# p6_wch_link.net
KiCad netlist of a schematic drawn in Altium Designer
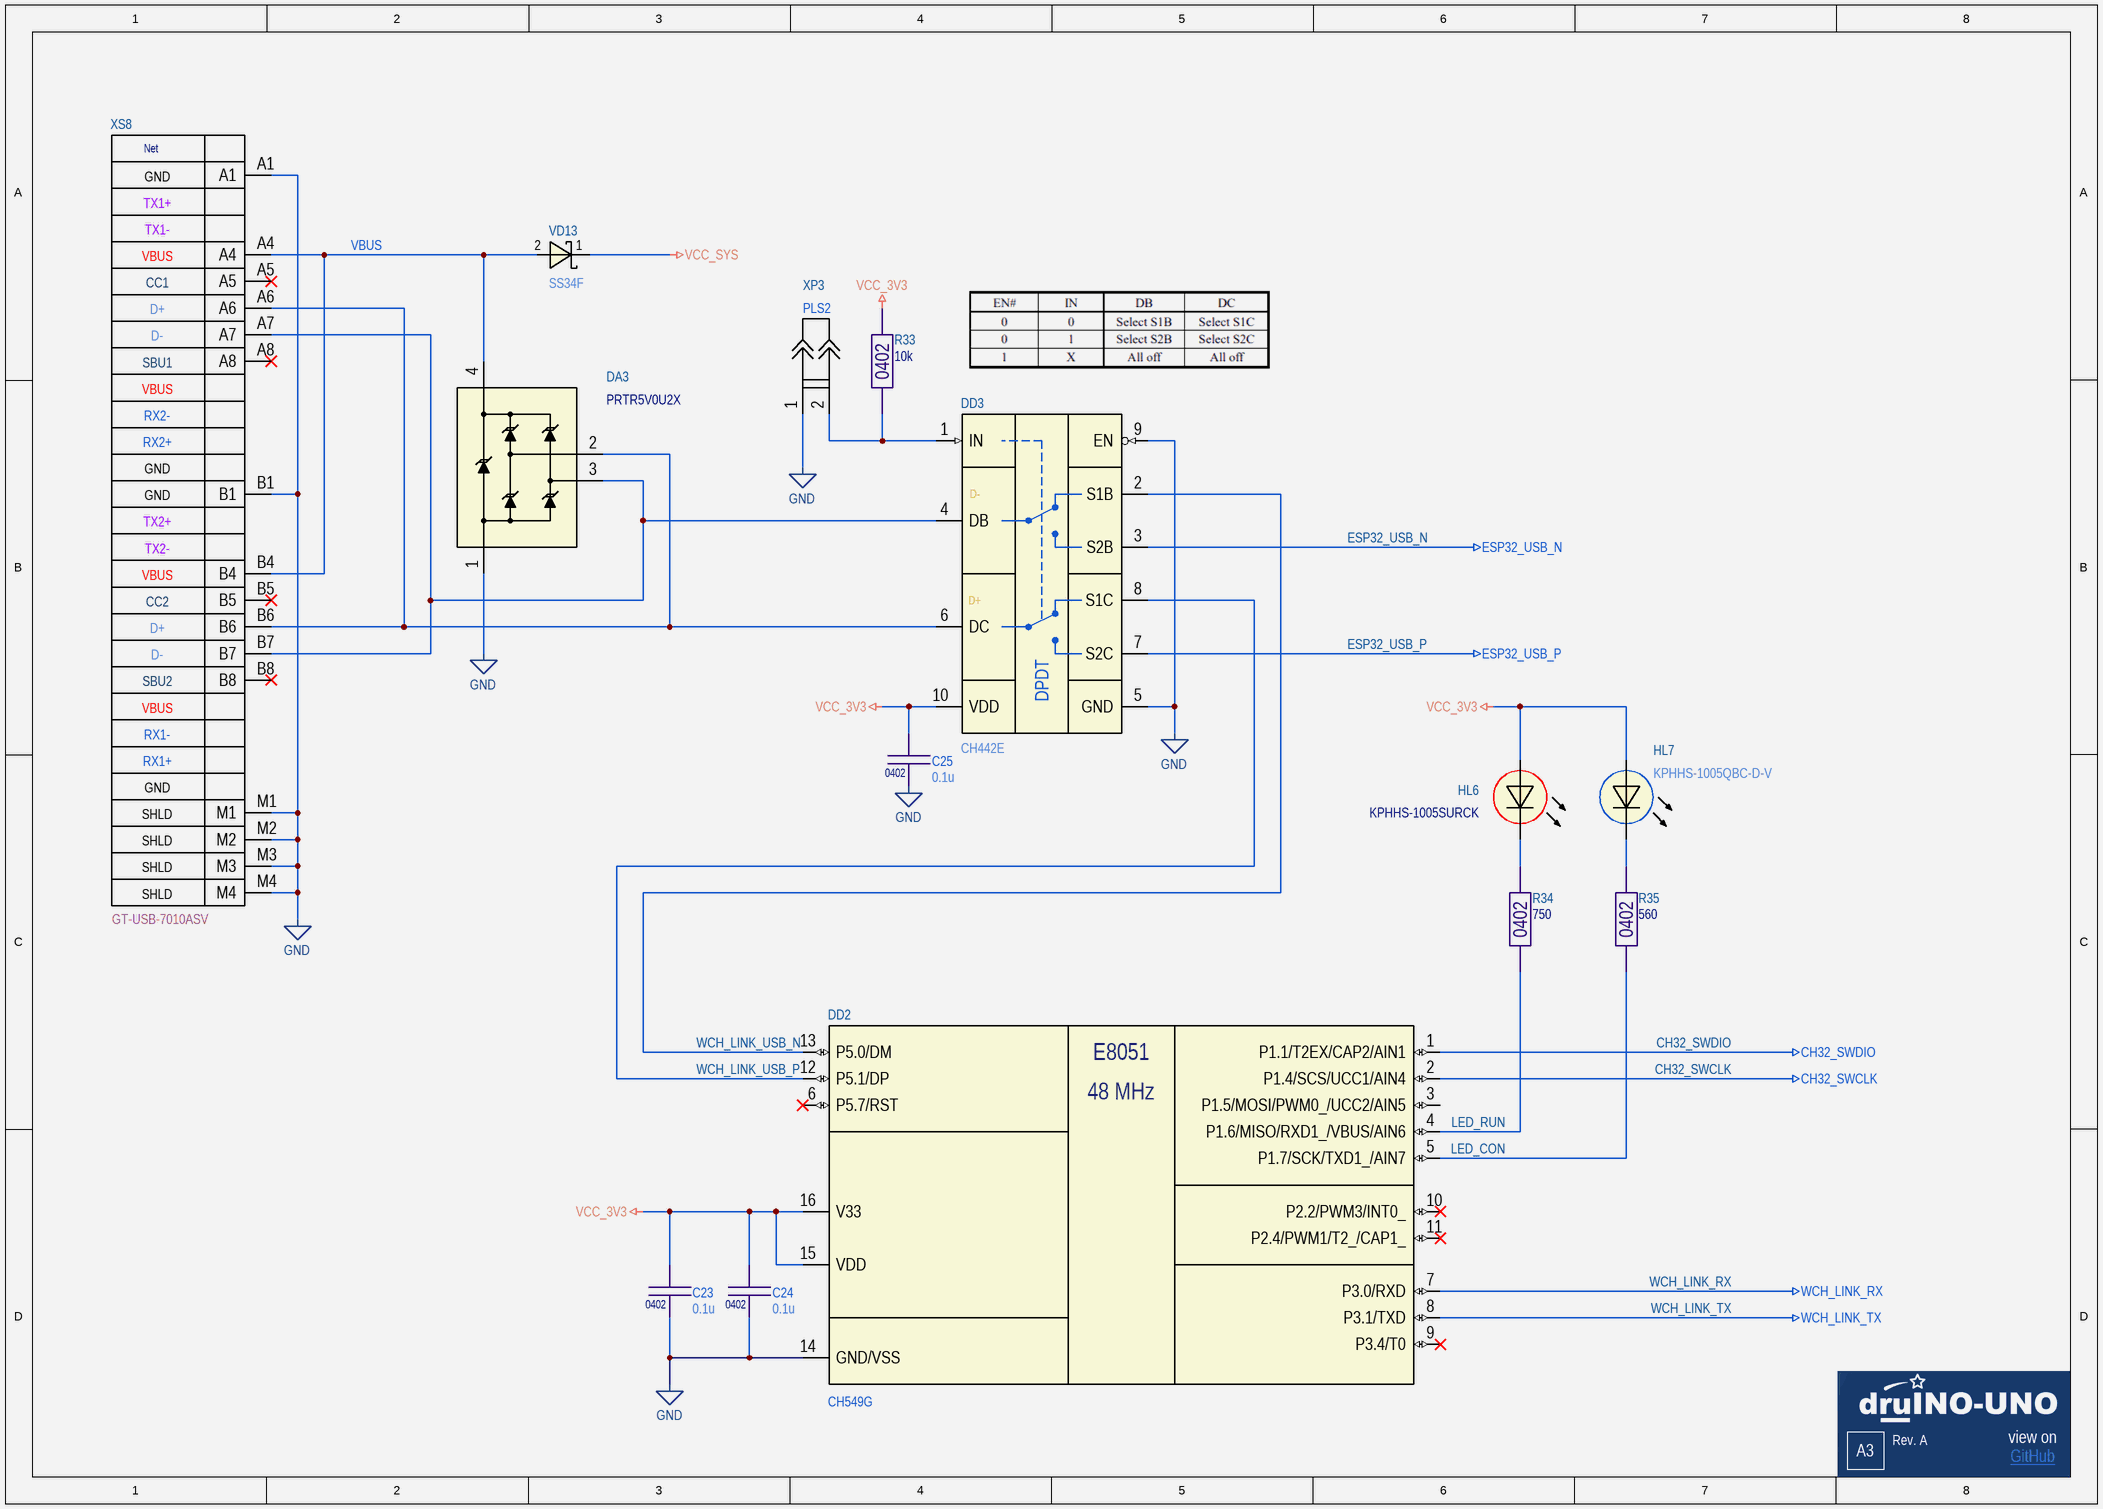
[diagram p0: p6_wch_link.SchDoc]

(export (version "E")
  (design (tool "Eeschema 10.0.6"))
  (components
    (comp (ref "C23")
      (value "0.1u")
      (footprint "PcbLib_RC:CAP0402")
      (description "Capacitors 0402 package case")
      (fields
        (field (name "TOLERANCE") "± 5 %")
        (field (name "VOLTAGE") "50 V")
        (field (name "PACKAGE") "0402")
      )
      (libsource (lib "Schlib_RC") (part "C0402"))
    )
    (comp (ref "C24")
      (value "0.1u")
      (footprint "PcbLib_RC:CAP0402")
      (description "Capacitors 0402 package case")
      (fields
        (field (name "TOLERANCE") "± 5 %")
        (field (name "VOLTAGE") "50 V")
        (field (name "PACKAGE") "0402")
      )
      (libsource (lib "Schlib_RC") (part "C0402"))
    )
    (comp (ref "C25")
      (value "0.1u")
      (footprint "PcbLib_RC:CAP0402")
      (description "Capacitors 0402 package case")
      (fields
        (field (name "TOLERANCE") "± 5 %")
        (field (name "VOLTAGE") "50 V")
        (field (name "PACKAGE") "0402")
      )
      (libsource (lib "Schlib_RC") (part "C0402"))
    )
    (comp (ref "DA3")
      (value "PRTR5V0U2X")
      (footprint "PcbLib_ICs:SOT143")
      (description "Ultra low capacitance double rail-to-rail ESD protection diode")
      (fields (field (name "MANUFACTURER") "NXP USA Inc."))
      (libsource (lib "Schlib_NXP_Semiconductors") (part "PRTR5V0U2X"))
    )
    (comp (ref "DD2")
      (value "CH549G")
      (footprint "PcbLib_ICs:SOIC-16")
      (description "8-bit Enhanced USB MCU")
      (fields (field (name "MANUFACTURER") "WinChipHead"))
      (libsource (lib "Schlib_WCH") (part "CH549G"))
    )
    (comp (ref "DD3")
      (value "CH442E")
      (footprint "PcbLib_ICs:MSOP-10")
      (description "Double-pole Double-throw Low-Resistance Analog Switch IC")
      (fields (field (name "MANUFACTURER") "WinChipHead"))
      (libsource (lib "Schlib_WCH") (part "CH442E"))
    )
    (comp (ref "HL6")
      (value "KPHHS-1005SURCK")
      (footprint "PcbLib_Others:LED0402R")
      (description "Red led (package case 0402)")
      (fields (field (name "MANUFACTURER") "Kingbright Company LLC."))
      (libsource (lib "Schlib_Kingbright") (part "KPHHS-1005SURCK"))
    )
    (comp (ref "HL7")
      (value "KPHHS-1005QBC-D-V")
      (footprint "PcbLib_Others:LED0402B")
      (description "Blue led (package case 0402)")
      (fields (field (name "MANUFACTURER") "Kingbright Company LLC."))
      (libsource (lib "Schlib_Kingbright") (part "KPHHS-1005QBC-D-V"))
    )
    (comp (ref "R33")
      (value "10k")
      (footprint "PcbLib_RC:RES0402B")
      (description "Resistor 0402 package case")
      (fields
        (field (name "TOLERANCE") "± 1 %")
        (field (name "PART NUMBER") "RC0402FR-0710KL")
        (field (name "PACKAGE") "0402")
      )
      (libsource (lib "Schlib_RC") (part "R0402"))
    )
    (comp (ref "R34")
      (value "750")
      (footprint "PcbLib_RC:RES0402B")
      (description "Resistor 0402 package case")
      (fields
        (field (name "TOLERANCE") "± 1 %")
        (field (name "PART NUMBER") "RC0402FR-07750RL")
        (field (name "PACKAGE") "0402")
      )
      (libsource (lib "Schlib_RC") (part "R0402"))
    )
    (comp (ref "R35")
      (value "560")
      (footprint "PcbLib_RC:RES0402B")
      (description "Resistor 0402 package case")
      (fields
        (field (name "TOLERANCE") "± 1 %")
        (field (name "PART NUMBER") "RC0402FR-07560RL")
        (field (name "PACKAGE") "0402")
      )
      (libsource (lib "Schlib_RC") (part "R0402"))
    )
    (comp (ref "VD13")
      (value "SS34F")
      (footprint "PcbLib_Discrete:SMA-FL")
      (description "3A Schottky barrier rectifier")
      (fields (field (name "MANUFACTURER") "UMW"))
      (libsource (lib "Schlib_UMW") (part "SS34F"))
    )
    (comp (ref "XP3")
      (value "PLS2")
      (footprint "PcbLib_Pin_Headers:PLS-2")
      (libsource (lib "Schlib_OtherComponents") (part "PLS2"))
    )
    (comp (ref "XS8")
      (value "GT-USB-7010ASV")
      (footprint "PcbLib_Connectors:GT-USB-7010ASV")
      (description "USB 2.0 Female 3A Surface 16P")
      (fields (field (name "MANUFACTURER") "G-Switch"))
      (libsource (lib "Schlib_OtherComponents") (part "GT-USB-7010ASV"))
    )
  )
  (nets
    (net (code "1") (name "/LED_CON") (class "Default")
      (node (ref "DD2") (pin "5") (pinfunction "P1.7/SCK/TXD1_/AIN7_5") (pintype "bidirectional"))
      (node (ref "R35") (pin "2") (pinfunction "2_2") (pintype "passive"))
    )
    (net (code "2") (name "/LED_RUN") (class "Default")
      (node (ref "DD2") (pin "4") (pinfunction "P1.6/MISO/RXD1_/VBUS/AIN6_4") (pintype "bidirectional"))
      (node (ref "R34") (pin "2") (pinfunction "2_2") (pintype "passive"))
    )
    (net (code "3") (name "/VBUS") (class "Default")
      (node (ref "DA3") (pin "4") (pinfunction "VCC_4") (pintype "passive"))
      (node (ref "VD13") (pin "2") (pinfunction "2_2") (pintype "passive"))
      (node (ref "XS8") (pin "A4") (pinfunction "A4_A4") (pintype "passive"))
      (node (ref "XS8") (pin "B4") (pinfunction "B4_B4") (pintype "passive"))
    )
    (net (code "4") (name "/WCH_LINK_USB_N") (class "Default")
      (node (ref "DD2") (pin "13") (pinfunction "P5.0/DM_13") (pintype "bidirectional"))
      (node (ref "DD3") (pin "2") (pinfunction "S1B_2") (pintype "passive"))
    )
    (net (code "5") (name "/WCH_LINK_USB_P") (class "Default")
      (node (ref "DD2") (pin "12") (pinfunction "P5.1/DP_12") (pintype "bidirectional"))
      (node (ref "DD3") (pin "8") (pinfunction "S1C_8") (pintype "passive"))
    )
    (net (code "6") (name "CH32_SWCLK") (class "Default")
      (node (ref "DD2") (pin "2") (pinfunction "P1.4/SCS/UCC1/AIN4_2") (pintype "bidirectional"))
    )
    (net (code "7") (name "CH32_SWDIO") (class "Default")
      (node (ref "DD2") (pin "1") (pinfunction "P1.1/T2EX/CAP2/AIN1_1") (pintype "bidirectional"))
    )
    (net (code "8") (name "ESP32_USB_N") (class "Default")
      (node (ref "DD3") (pin "3") (pinfunction "S2B_3") (pintype "passive"))
    )
    (net (code "9") (name "ESP32_USB_P") (class "Default")
      (node (ref "DD3") (pin "7") (pinfunction "S2C_7") (pintype "passive"))
    )
    (net (code "10") (name "GND") (class "Default")
      (node (ref "C23") (pin "2") (pinfunction "2_2") (pintype "passive"))
      (node (ref "C24") (pin "2") (pinfunction "2_2") (pintype "passive"))
      (node (ref "C25") (pin "2") (pinfunction "2_2") (pintype "passive"))
      (node (ref "DA3") (pin "1") (pinfunction "GND_1") (pintype "passive"))
      (node (ref "DD2") (pin "14") (pinfunction "GND/VSS_14") (pintype "power_in"))
      (node (ref "DD3") (pin "5") (pinfunction "GND_5") (pintype "power_in"))
      (node (ref "DD3") (pin "9") (pinfunction "EN_9") (pintype "input"))
      (node (ref "XP3") (pin "1") (pinfunction "1_1") (pintype "passive"))
      (node (ref "XS8") (pin "A1") (pinfunction "A1_A1") (pintype "passive"))
      (node (ref "XS8") (pin "B1") (pinfunction "B1_B1") (pintype "passive"))
      (node (ref "XS8") (pin "M1") (pinfunction "M1_M1") (pintype "passive"))
      (node (ref "XS8") (pin "M2") (pinfunction "M2_M2") (pintype "passive"))
      (node (ref "XS8") (pin "M3") (pinfunction "M3_M3") (pintype "passive"))
      (node (ref "XS8") (pin "M4") (pinfunction "M4_M4") (pintype "passive"))
    )
    (net (code "11") (name "Net-(DA3-IO1)") (class "Default")
      (node (ref "DA3") (pin "2") (pinfunction "IO1_2") (pintype "passive"))
      (node (ref "DD3") (pin "6") (pinfunction "DC_6") (pintype "passive"))
      (node (ref "XS8") (pin "A6") (pinfunction "A6_A6") (pintype "passive"))
      (node (ref "XS8") (pin "B6") (pinfunction "B6_B6") (pintype "passive"))
    )
    (net (code "12") (name "Net-(DA3-IO2)") (class "Default")
      (node (ref "DA3") (pin "3") (pinfunction "IO2_3") (pintype "passive"))
      (node (ref "DD3") (pin "4") (pinfunction "DB_4") (pintype "passive"))
      (node (ref "XS8") (pin "A7") (pinfunction "A7_A7") (pintype "passive"))
      (node (ref "XS8") (pin "B7") (pinfunction "B7_B7") (pintype "passive"))
    )
    (net (code "13") (name "Net-(DD3-IN)") (class "Default")
      (node (ref "DD3") (pin "1") (pinfunction "IN_1") (pintype "input"))
      (node (ref "R33") (pin "2") (pinfunction "2_2") (pintype "passive"))
      (node (ref "XP3") (pin "2") (pinfunction "2_2") (pintype "passive"))
    )
    (net (code "14") (name "Net-(HL6-Pad1)") (class "Default")
      (node (ref "HL6") (pin "1") (pinfunction "1_1") (pintype "passive"))
      (node (ref "R34") (pin "1") (pinfunction "1_1") (pintype "passive"))
    )
    (net (code "15") (name "Net-(HL7-Pad1)") (class "Default")
      (node (ref "HL7") (pin "1") (pinfunction "1_1") (pintype "passive"))
      (node (ref "R35") (pin "1") (pinfunction "1_1") (pintype "passive"))
    )
    (net (code "16") (name "VCC_3V3") (class "Default")
      (node (ref "C23") (pin "1") (pinfunction "1_1") (pintype "passive"))
      (node (ref "C24") (pin "1") (pinfunction "1_1") (pintype "passive"))
      (node (ref "C25") (pin "1") (pinfunction "1_1") (pintype "passive"))
      (node (ref "DD2") (pin "15") (pinfunction "VDD_15") (pintype "power_in"))
      (node (ref "DD2") (pin "16") (pinfunction "V33_16") (pintype "power_in"))
      (node (ref "DD3") (pin "10") (pinfunction "VDD_10") (pintype "power_in"))
      (node (ref "HL6") (pin "2") (pinfunction "2_2") (pintype "passive"))
      (node (ref "HL7") (pin "2") (pinfunction "2_2") (pintype "passive"))
      (node (ref "R33") (pin "1") (pinfunction "1_1") (pintype "passive"))
    )
    (net (code "17") (name "VCC_SYS") (class "Default")
      (node (ref "VD13") (pin "1") (pinfunction "1_1") (pintype "passive"))
    )
    (net (code "18") (name "WCH_LINK_RX") (class "Default")
      (node (ref "DD2") (pin "7") (pinfunction "P3.0/RXD_7") (pintype "bidirectional"))
    )
    (net (code "19") (name "WCH_LINK_TX") (class "Default")
      (node (ref "DD2") (pin "8") (pinfunction "P3.1/TXD_8") (pintype "bidirectional"))
    )
    (net (code "20") (name "unconnected-(DD2-P1.5{slash}MOSI{slash}PWM0_{slash}UCC2{slash}AIN5-Pad3)") (class "Default")
      (node (ref "DD2") (pin "3") (pinfunction "P1.5/MOSI/PWM0_/UCC2/AIN5_3") (pintype "bidirectional"))
    )
    (net (code "21") (name "unconnected-(DD2-P2.2{slash}PWM3{slash}INT0_-Pad10)") (class "Default")
      (node (ref "DD2") (pin "10") (pinfunction "P2.2/PWM3/INT0__10") (pintype "bidirectional+no_connect"))
    )
    (net (code "22") (name "unconnected-(DD2-P2.4{slash}PWM1{slash}T2_{slash}CAP1_-Pad11)") (class "Default")
      (node (ref "DD2") (pin "11") (pinfunction "P2.4/PWM1/T2_/CAP1__11") (pintype "bidirectional+no_connect"))
    )
    (net (code "23") (name "unconnected-(DD2-P3.4{slash}T0-Pad9)") (class "Default")
      (node (ref "DD2") (pin "9") (pinfunction "P3.4/T0_9") (pintype "bidirectional+no_connect"))
    )
    (net (code "24") (name "unconnected-(DD2-P5.7{slash}RST-Pad6)") (class "Default")
      (node (ref "DD2") (pin "6") (pinfunction "P5.7/RST_6") (pintype "bidirectional+no_connect"))
    )
    (net (code "25") (name "unconnected-(XS8-PadA5)") (class "Default")
      (node (ref "XS8") (pin "A5") (pinfunction "A5_A5") (pintype "passive+no_connect"))
    )
    (net (code "26") (name "unconnected-(XS8-PadA8)") (class "Default")
      (node (ref "XS8") (pin "A8") (pinfunction "A8_A8") (pintype "passive+no_connect"))
    )
    (net (code "27") (name "unconnected-(XS8-PadB5)") (class "Default")
      (node (ref "XS8") (pin "B5") (pinfunction "B5_B5") (pintype "passive+no_connect"))
    )
    (net (code "28") (name "unconnected-(XS8-PadB8)") (class "Default")
      (node (ref "XS8") (pin "B8") (pinfunction "B8_B8") (pintype "passive+no_connect"))
    )
  )
)
